# Multivibrator.net
KiCad netlist of a schematic drawn in Altium Designer
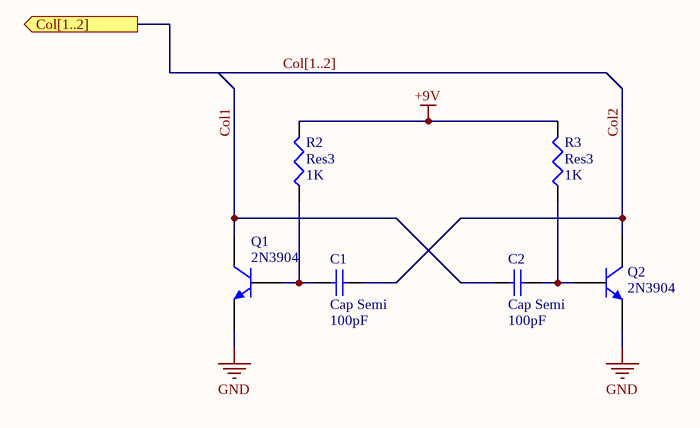
[diagram p0: Multivibrator.SchDoc]

(export (version "E")
  (design (tool "Eeschema 10.0.6"))
  (components
    (comp (ref "C1")
      (value "Cap Semi")
      (footprint "C1206")
      (description "Capacitor (Semiconductor SIM Model)")
      (fields (field (name "ALTIUM_VALUE") "100pF") (field (name "PUBLISHER") "Altium Limited"))
      (libsource (lib "Miscellaneous Devices") (part "Cap Semi"))
    )
    (comp (ref "C2")
      (value "Cap Semi")
      (footprint "C1206")
      (description "Capacitor (Semiconductor SIM Model)")
      (fields (field (name "ALTIUM_VALUE") "100pF") (field (name "PUBLISHER") "Altium Limited"))
      (libsource (lib "Miscellaneous Devices") (part "Cap Semi"))
    )
    (comp (ref "Q1")
      (value "2N3904")
      (footprint "TO-92A")
      (description "NPN General Purpose Amplifier")
      (fields (field (name "PUBLISHER") "Altium Limited"))
      (libsource (lib "Miscellaneous Devices") (part "2N3904"))
    )
    (comp (ref "Q2")
      (value "2N3904")
      (footprint "TO-92A")
      (description "NPN General Purpose Amplifier")
      (fields (field (name "PUBLISHER") "Altium Limited"))
      (libsource (lib "Miscellaneous Devices") (part "2N3904"))
    )
    (comp (ref "R2")
      (value "Res3")
      (footprint "J1-0603")
      (description "Resistor")
      (fields (field (name "ALTIUM_VALUE") "1K") (field (name "PUBLISHER") "Altium Limited"))
      (libsource (lib "Miscellaneous Devices") (part "Res3"))
    )
    (comp (ref "R3")
      (value "Res3")
      (footprint "J1-0603")
      (description "Resistor")
      (fields (field (name "ALTIUM_VALUE") "1K") (field (name "PUBLISHER") "Altium Limited"))
      (libsource (lib "Miscellaneous Devices") (part "Res3"))
    )
  )
  (nets
    (net (code "1") (name "+9V") (class "Default")
      (node (ref "R2") (pin "2") (pinfunction "2_2") (pintype "passive"))
      (node (ref "R3") (pin "2") (pinfunction "2_2") (pintype "passive"))
    )
    (net (code "2") (name "/Col1") (class "Default")
      (node (ref "C2") (pin "1") (pinfunction "1_1") (pintype "passive"))
      (node (ref "Q1") (pin "3") (pinfunction "C_3") (pintype "passive"))
    )
    (net (code "3") (name "/Col2") (class "Default")
      (node (ref "C1") (pin "2") (pinfunction "2_2") (pintype "passive"))
      (node (ref "Q2") (pin "3") (pinfunction "C_3") (pintype "passive"))
    )
    (net (code "5") (name "GND") (class "Default")
      (node (ref "Q1") (pin "1") (pinfunction "E_1") (pintype "passive"))
      (node (ref "Q2") (pin "1") (pinfunction "E_1") (pintype "passive"))
    )
    (net (code "6") (name "Net-(Q1-B)") (class "Default")
      (node (ref "C1") (pin "1") (pinfunction "1_1") (pintype "passive"))
      (node (ref "Q1") (pin "2") (pinfunction "B_2") (pintype "passive"))
      (node (ref "R2") (pin "1") (pinfunction "1_1") (pintype "passive"))
    )
    (net (code "7") (name "Net-(Q2-B)") (class "Default")
      (node (ref "C2") (pin "2") (pinfunction "2_2") (pintype "passive"))
      (node (ref "Q2") (pin "2") (pinfunction "B_2") (pintype "passive"))
      (node (ref "R3") (pin "1") (pinfunction "1_1") (pintype "passive"))
    )
  )
)
